# input19-21.net
KiCad netlist of a schematic drawn in Altium Designer
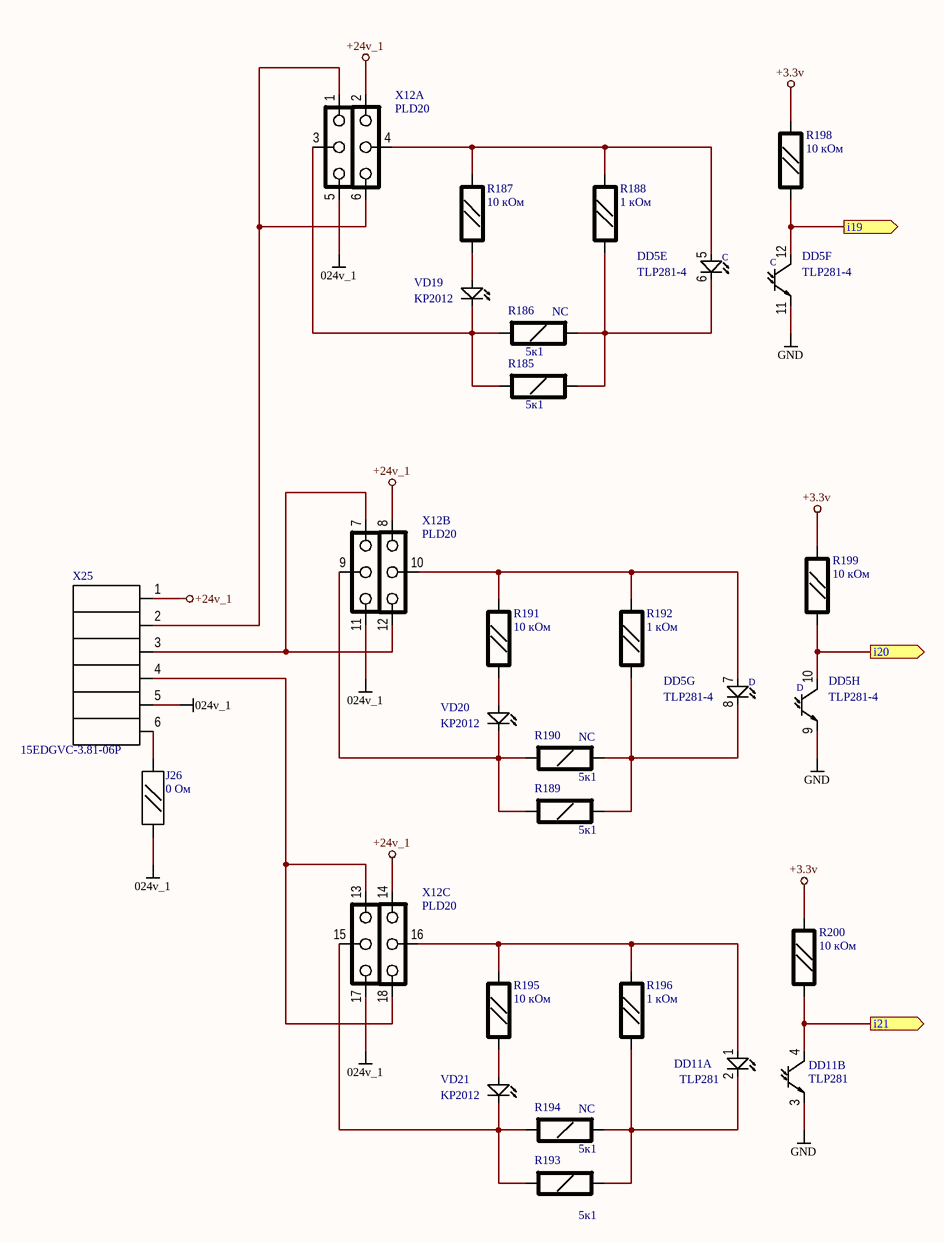
[diagram p0: input19-21.SchDoc]

(export (version "E")
  (design (tool "Eeschema 10.0.6"))
  (components
    (comp (ref "DD5")
      (value "TLP281-4")
      (footprint "SO16")
      (description "4х канальная транзисторная оптопара")
      (fields (field (name "VOLTAGE") "80V"))
      (libsource (lib "L02_22F") (part "TLP281-4"))
    )
    (comp (ref "DD11")
      (value "TLP281")
      (footprint "SOIC4")
      (description "Оптопара транзисторная")
      (fields (field (name "VOLTAGE") "80V"))
      (libsource (lib "L02_22F") (part "TLP281"))
    )
    (comp (ref "J26")
      (value "0 Ом")
      (footprint "SMD0805RES")
      (description "SMD 0805 перемычка")
      (libsource (lib "iL03_22") (part "JR0805"))
    )
    (comp (ref "R185")
      (value "5к1")
      (footprint "RES1206")
      (description "Чип резистор 1206")
      (fields (field (name "TOLERANCE") "5%"))
      (libsource (lib "SL02_22F") (part "R1206"))
    )
    (comp (ref "R186")
      (value "5к1")
      (footprint "RES1206")
      (description "Чип резистор 1206")
      (fields (field (name "TOLERANCE") "5%") (field (name "SOLDEROPTON") "NC"))
      (libsource (lib "SL02_22F") (part "R1206"))
    )
    (comp (ref "R187")
      (value "10 кОм")
      (footprint "SMD0805RES")
      (description "Чип резистор 0805")
      (fields (field (name "TOLERANCE") "5%"))
      (libsource (lib "SL02_22F") (part "R0805"))
    )
    (comp (ref "R188")
      (value "1 кОм")
      (footprint "SMD0805RES")
      (description "Чип резистор 0805")
      (fields (field (name "TOLERANCE") "5%"))
      (libsource (lib "SL02_22F") (part "R0805"))
    )
    (comp (ref "R189")
      (value "5к1")
      (footprint "RES1206")
      (description "Чип резистор 1206")
      (fields (field (name "TOLERANCE") "5%"))
      (libsource (lib "SL02_22F") (part "R1206"))
    )
    (comp (ref "R190")
      (value "5к1")
      (footprint "RES1206")
      (description "Чип резистор 1206")
      (fields (field (name "TOLERANCE") "5%") (field (name "SOLDEROPTON") "NC"))
      (libsource (lib "SL02_22F") (part "R1206"))
    )
    (comp (ref "R191")
      (value "10 кОм")
      (footprint "SMD0805RES")
      (description "Чип резистор 0805")
      (fields (field (name "TOLERANCE") "5%"))
      (libsource (lib "SL02_22F") (part "R0805"))
    )
    (comp (ref "R192")
      (value "1 кОм")
      (footprint "SMD0805RES")
      (description "Чип резистор 0805")
      (fields (field (name "TOLERANCE") "5%"))
      (libsource (lib "SL02_22F") (part "R0805"))
    )
    (comp (ref "R193")
      (value "5к1")
      (footprint "RES1206")
      (description "Чип резистор 1206")
      (fields (field (name "TOLERANCE") "5%"))
      (libsource (lib "SL02_22F") (part "R1206"))
    )
    (comp (ref "R194")
      (value "5к1")
      (footprint "RES1206")
      (description "Чип резистор 1206")
      (fields (field (name "TOLERANCE") "5%") (field (name "SOLDEROPTON") "NC"))
      (libsource (lib "SL02_22F") (part "R1206"))
    )
    (comp (ref "R195")
      (value "10 кОм")
      (footprint "SMD0805RES")
      (description "Чип резистор 0805")
      (fields (field (name "TOLERANCE") "5%"))
      (libsource (lib "SL02_22F") (part "R0805"))
    )
    (comp (ref "R196")
      (value "1 кОм")
      (footprint "SMD0805RES")
      (description "Чип резистор 0805")
      (fields (field (name "TOLERANCE") "5%"))
      (libsource (lib "SL02_22F") (part "R0805"))
    )
    (comp (ref "R198")
      (value "10 кОм")
      (footprint "SMD0805RES")
      (description "Чип резистор 0805")
      (fields (field (name "TOLERANCE") "5%"))
      (libsource (lib "SL02_22F") (part "R0805"))
    )
    (comp (ref "R199")
      (value "10 кОм")
      (footprint "SMD0805RES")
      (description "Чип резистор 0805")
      (fields (field (name "TOLERANCE") "5%"))
      (libsource (lib "SL02_22F") (part "R0805"))
    )
    (comp (ref "R200")
      (value "10 кОм")
      (footprint "SMD0805RES")
      (description "Чип резистор 0805")
      (fields (field (name "TOLERANCE") "5%"))
      (libsource (lib "SL02_22F") (part "R0805"))
    )
    (comp (ref "VD19")
      (value "KP2012")
      (footprint "SMD0805DIO_C")
      (description "Чип светодиод 0805")
      (libsource (lib "L02_22F") (part "KP2012_C"))
    )
    (comp (ref "VD20")
      (value "KP2012")
      (footprint "SMD0805DIO_C")
      (description "Чип светодиод 0805")
      (libsource (lib "L02_22F") (part "KP2012_C"))
    )
    (comp (ref "VD21")
      (value "KP2012")
      (footprint "SMD0805DIO_C")
      (description "Чип светодиод 0805")
      (libsource (lib "L02_22F") (part "KP2012_C"))
    )
    (comp (ref "X12")
      (value "PLD20")
      (footprint "pld2x10_1.27")
      (description "Вилка  PLD 20/1.27")
      (libsource (lib "SL02_22F") (part "PLD20"))
    )
    (comp (ref "X25")
      (value "15EDGVC-3.81-06P")
      (footprint "15EDGVC_081_6")
      (description "Вилка  6/3.81")
      (fields (field (name "VOLTAGE") "2кВ"))
      (libsource (lib "L02_22F") (part "15EDGVC-3.81-06P"))
    )
  )
  (nets
    (net (code "1") (name "+3.3v") (class "Default")
      (node (ref "R198") (pin "2") (pinfunction "2_2") (pintype "passive"))
      (node (ref "R199") (pin "2") (pinfunction "2_2") (pintype "passive"))
      (node (ref "R200") (pin "2") (pinfunction "2_2") (pintype "passive"))
    )
    (net (code "2") (name "+24v_1") (class "Default")
      (node (ref "X12") (pin "14") (pinfunction "14_14") (pintype "passive"))
      (node (ref "X12") (pin "2") (pinfunction "2_2") (pintype "passive"))
      (node (ref "X12") (pin "8") (pinfunction "8_8") (pintype "passive"))
      (node (ref "X25") (pin "1") (pinfunction "1_1") (pintype "passive"))
    )
    (net (code "3") (name "/i19") (class "Default")
      (node (ref "DD5") (pin "12") (pinfunction "Collector_C_12") (pintype "passive"))
      (node (ref "R198") (pin "1") (pinfunction "1_1") (pintype "passive"))
    )
    (net (code "4") (name "/i20") (class "Default")
      (node (ref "DD5") (pin "10") (pinfunction "Collector_D_10") (pintype "passive"))
      (node (ref "R199") (pin "1") (pinfunction "1_1") (pintype "passive"))
    )
    (net (code "5") (name "/i21") (class "Default")
      (node (ref "DD11") (pin "4") (pinfunction "Collector_4") (pintype "passive"))
      (node (ref "R200") (pin "1") (pinfunction "1_1") (pintype "passive"))
    )
    (net (code "6") (name "024v_1") (class "Default")
      (node (ref "J26") (pin "2") (pinfunction "2_2") (pintype "passive"))
      (node (ref "X12") (pin "11") (pinfunction "11_11") (pintype "passive"))
      (node (ref "X12") (pin "17") (pinfunction "17_17") (pintype "passive"))
      (node (ref "X12") (pin "5") (pinfunction "5_5") (pintype "passive"))
      (node (ref "X25") (pin "5") (pinfunction "5_5") (pintype "passive"))
    )
    (net (code "7") (name "GND") (class "Default")
      (node (ref "DD11") (pin "3") (pinfunction "Emitter_3") (pintype "passive"))
      (node (ref "DD5") (pin "11") (pinfunction "Emitter_C_11") (pintype "passive"))
      (node (ref "DD5") (pin "9") (pinfunction "Emitter_D_9") (pintype "passive"))
    )
    (net (code "8") (name "Net-(DD5E-Anode_C)") (class "Default")
      (node (ref "DD5") (pin "5") (pinfunction "Anode_C_5") (pintype "passive"))
      (node (ref "R187") (pin "1") (pinfunction "1_1") (pintype "passive"))
      (node (ref "R188") (pin "1") (pinfunction "1_1") (pintype "passive"))
      (node (ref "X12") (pin "4") (pinfunction "4_4") (pintype "passive"))
    )
    (net (code "9") (name "Net-(DD5E-Cathode)") (class "Default")
      (node (ref "DD5") (pin "6") (pinfunction "Cathode_6") (pintype "passive"))
      (node (ref "R185") (pin "2") (pinfunction "2_2") (pintype "passive"))
      (node (ref "R186") (pin "2") (pinfunction "2_2") (pintype "passive"))
      (node (ref "R188") (pin "2") (pinfunction "2_2") (pintype "passive"))
    )
    (net (code "10") (name "Net-(DD5G-Anode_D)") (class "Default")
      (node (ref "DD5") (pin "7") (pinfunction "Anode_D_7") (pintype "passive"))
      (node (ref "R191") (pin "1") (pinfunction "1_1") (pintype "passive"))
      (node (ref "R192") (pin "1") (pinfunction "1_1") (pintype "passive"))
      (node (ref "X12") (pin "10") (pinfunction "10_10") (pintype "passive"))
    )
    (net (code "11") (name "Net-(DD5G-Cathode_D)") (class "Default")
      (node (ref "DD5") (pin "8") (pinfunction "Cathode_D_8") (pintype "passive"))
      (node (ref "R189") (pin "2") (pinfunction "2_2") (pintype "passive"))
      (node (ref "R190") (pin "2") (pinfunction "2_2") (pintype "passive"))
      (node (ref "R192") (pin "2") (pinfunction "2_2") (pintype "passive"))
    )
    (net (code "12") (name "Net-(DD11A-Anode)") (class "Default")
      (node (ref "DD11") (pin "1") (pinfunction "Anode_1") (pintype "passive"))
      (node (ref "R195") (pin "1") (pinfunction "1_1") (pintype "passive"))
      (node (ref "R196") (pin "1") (pinfunction "1_1") (pintype "passive"))
      (node (ref "X12") (pin "16") (pinfunction "16_16") (pintype "passive"))
    )
    (net (code "13") (name "Net-(DD11A-Cathode)") (class "Default")
      (node (ref "DD11") (pin "2") (pinfunction "Cathode_2") (pintype "passive"))
      (node (ref "R193") (pin "2") (pinfunction "2_2") (pintype "passive"))
      (node (ref "R194") (pin "2") (pinfunction "2_2") (pintype "passive"))
      (node (ref "R196") (pin "2") (pinfunction "2_2") (pintype "passive"))
    )
    (net (code "14") (name "Net-(J26-Pad1)") (class "Default")
      (node (ref "J26") (pin "1") (pinfunction "1_1") (pintype "passive"))
      (node (ref "X25") (pin "6") (pinfunction "6_6") (pintype "passive"))
    )
    (net (code "15") (name "Net-(VD19-Anode)") (class "Default")
      (node (ref "R187") (pin "2") (pinfunction "2_2") (pintype "passive"))
      (node (ref "VD19") (pin "2") (pinfunction "Anode_2") (pintype "passive"))
    )
    (net (code "16") (name "Net-(VD19-Cathode)") (class "Default")
      (node (ref "R185") (pin "1") (pinfunction "1_1") (pintype "passive"))
      (node (ref "R186") (pin "1") (pinfunction "1_1") (pintype "passive"))
      (node (ref "VD19") (pin "1") (pinfunction "Cathode_1") (pintype "passive"))
      (node (ref "X12") (pin "3") (pinfunction "3_3") (pintype "passive"))
    )
    (net (code "17") (name "Net-(VD20-Anode)") (class "Default")
      (node (ref "R191") (pin "2") (pinfunction "2_2") (pintype "passive"))
      (node (ref "VD20") (pin "2") (pinfunction "Anode_2") (pintype "passive"))
    )
    (net (code "18") (name "Net-(VD20-Cathode)") (class "Default")
      (node (ref "R189") (pin "1") (pinfunction "1_1") (pintype "passive"))
      (node (ref "R190") (pin "1") (pinfunction "1_1") (pintype "passive"))
      (node (ref "VD20") (pin "1") (pinfunction "Cathode_1") (pintype "passive"))
      (node (ref "X12") (pin "9") (pinfunction "9_9") (pintype "passive"))
    )
    (net (code "19") (name "Net-(VD21-Anode)") (class "Default")
      (node (ref "R195") (pin "2") (pinfunction "2_2") (pintype "passive"))
      (node (ref "VD21") (pin "2") (pinfunction "Anode_2") (pintype "passive"))
    )
    (net (code "20") (name "Net-(VD21-Cathode)") (class "Default")
      (node (ref "R193") (pin "1") (pinfunction "1_1") (pintype "passive"))
      (node (ref "R194") (pin "1") (pinfunction "1_1") (pintype "passive"))
      (node (ref "VD21") (pin "1") (pinfunction "Cathode_1") (pintype "passive"))
      (node (ref "X12") (pin "15") (pinfunction "15_15") (pintype "passive"))
    )
    (net (code "21") (name "Net-(X12-Pad1)") (class "Default")
      (node (ref "X12") (pin "1") (pinfunction "1_1") (pintype "passive"))
      (node (ref "X12") (pin "6") (pinfunction "6_6") (pintype "passive"))
      (node (ref "X25") (pin "2") (pinfunction "2_2") (pintype "passive"))
    )
    (net (code "22") (name "Net-(X12-Pad12)") (class "Default")
      (node (ref "X12") (pin "12") (pinfunction "12_12") (pintype "passive"))
      (node (ref "X12") (pin "7") (pinfunction "7_7") (pintype "passive"))
      (node (ref "X25") (pin "3") (pinfunction "3_3") (pintype "passive"))
    )
    (net (code "23") (name "Net-(X12-Pad13)") (class "Default")
      (node (ref "X12") (pin "13") (pinfunction "13_13") (pintype "passive"))
      (node (ref "X12") (pin "18") (pinfunction "18_18") (pintype "passive"))
      (node (ref "X25") (pin "4") (pinfunction "4_4") (pintype "passive"))
    )
  )
)
